# IrLedJig.net
KiCad netlist of a schematic drawn in EAGLE
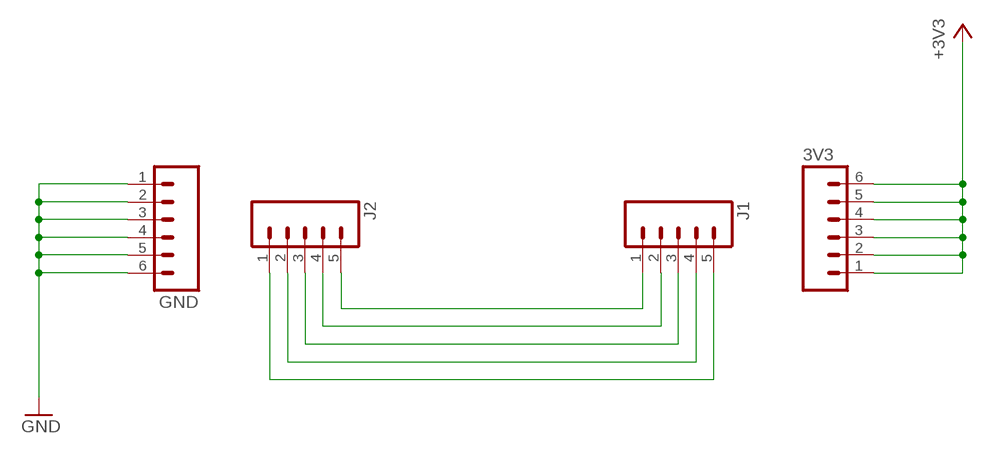
[diagram p0: schematic, sheet 1]

(export (version "E")
  (design (tool "Eeschema 10.0.6"))
  (components
    (comp (ref "3V3")
      (value "M06LOCK")
      (footprint "eagle-import:1X06_LOCK")
      (libsource (lib "eagle-import") (part "M06LOCK"))
    )
    (comp (ref "GND")
      (value "M06LOCK")
      (footprint "eagle-import:1X06_LOCK")
      (libsource (lib "eagle-import") (part "M06LOCK"))
    )
    (comp (ref "J1")
      (value "M05LOCK")
      (footprint "eagle-import:1X05_LOCK")
      (libsource (lib "eagle-import") (part "M05LOCK"))
    )
    (comp (ref "J2")
      (value "M05LOCK")
      (footprint "eagle-import:1X05_LOCK")
      (libsource (lib "eagle-import") (part "M05LOCK"))
    )
  )
  (nets
    (net (code "1") (name "+3V3") (class "Default")
      (node (ref "3V3") (pin "1") (pinfunction "1_1") (pintype "passive"))
      (node (ref "3V3") (pin "2") (pinfunction "2_2") (pintype "passive"))
      (node (ref "3V3") (pin "3") (pinfunction "3_3") (pintype "passive"))
      (node (ref "3V3") (pin "4") (pinfunction "4_4") (pintype "passive"))
      (node (ref "3V3") (pin "5") (pinfunction "5_5") (pintype "passive"))
      (node (ref "3V3") (pin "6") (pinfunction "6_6") (pintype "passive"))
    )
    (net (code "2") (name "GND") (class "Default")
      (node (ref "GND") (pin "1") (pinfunction "1_1") (pintype "passive"))
      (node (ref "GND") (pin "2") (pinfunction "2_2") (pintype "passive"))
      (node (ref "GND") (pin "3") (pinfunction "3_3") (pintype "passive"))
      (node (ref "GND") (pin "4") (pinfunction "4_4") (pintype "passive"))
      (node (ref "GND") (pin "5") (pinfunction "5_5") (pintype "passive"))
      (node (ref "GND") (pin "6") (pinfunction "6_6") (pintype "passive"))
    )
    (net (code "3") (name "Net-(J1-Pad1)") (class "Default")
      (node (ref "J1") (pin "1") (pinfunction "1_1") (pintype "passive"))
      (node (ref "J2") (pin "5") (pinfunction "5_5") (pintype "passive"))
    )
    (net (code "4") (name "Net-(J1-Pad2)") (class "Default")
      (node (ref "J1") (pin "2") (pinfunction "2_2") (pintype "passive"))
      (node (ref "J2") (pin "4") (pinfunction "4_4") (pintype "passive"))
    )
    (net (code "5") (name "Net-(J1-Pad3)") (class "Default")
      (node (ref "J1") (pin "3") (pinfunction "3_3") (pintype "passive"))
      (node (ref "J2") (pin "3") (pinfunction "3_3") (pintype "passive"))
    )
    (net (code "6") (name "Net-(J1-Pad4)") (class "Default")
      (node (ref "J1") (pin "4") (pinfunction "4_4") (pintype "passive"))
      (node (ref "J2") (pin "2") (pinfunction "2_2") (pintype "passive"))
    )
    (net (code "7") (name "Net-(J1-Pad5)") (class "Default")
      (node (ref "J1") (pin "5") (pinfunction "5_5") (pintype "passive"))
      (node (ref "J2") (pin "1") (pinfunction "1_1") (pintype "passive"))
    )
  )
)
